# ZED-F9R_v3.net
KiCad netlist of a schematic drawn in EAGLE
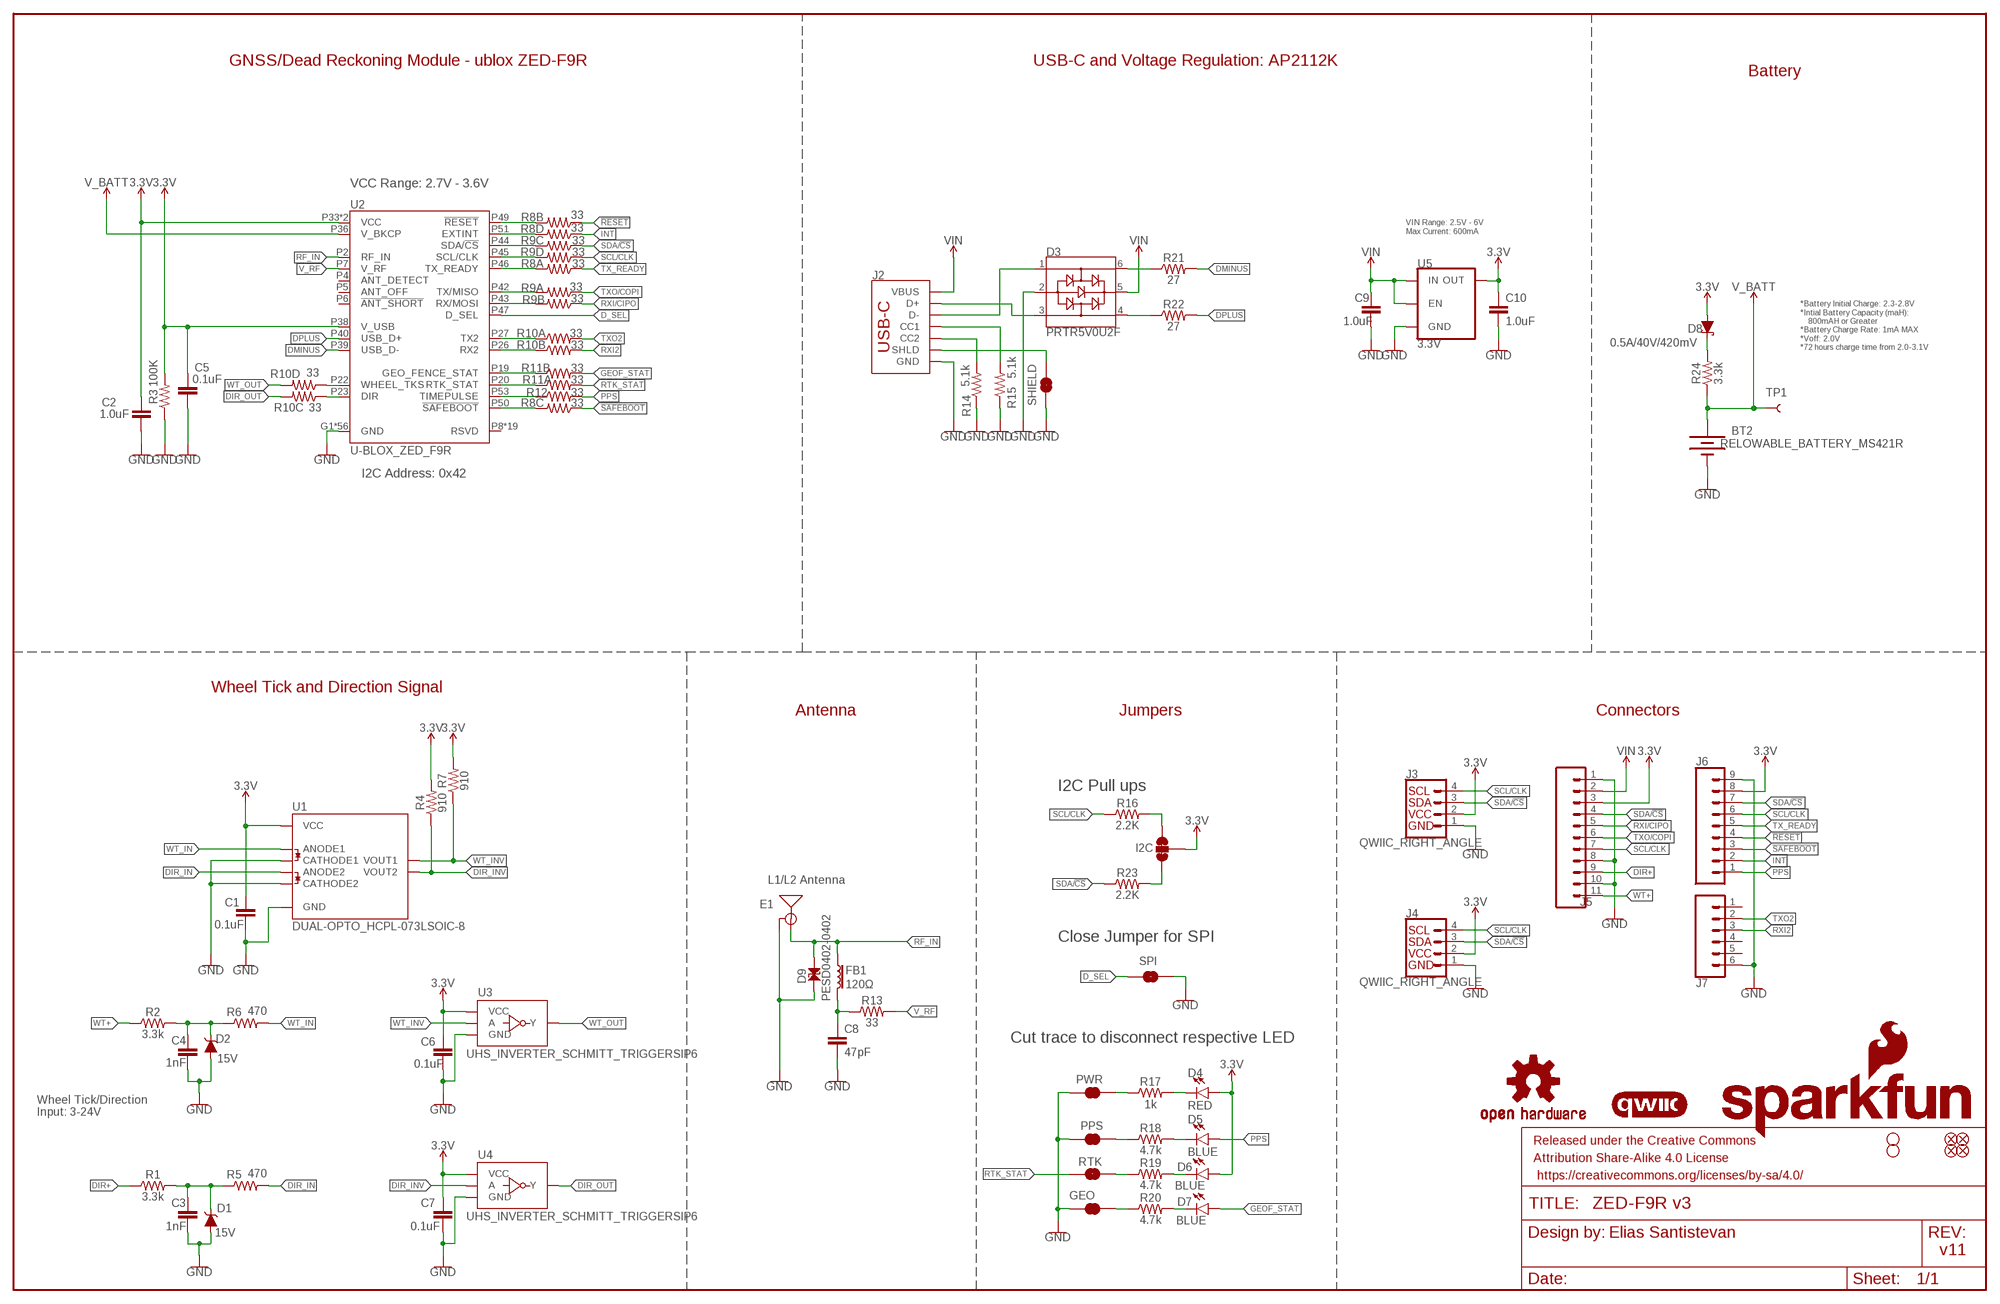
[diagram p0: schematic, sheet 1]

(export (version "E")
  (design (tool "Eeschema 10.0.6"))
  (components
    (comp (ref "$1_25_$_2020-03-30_22-52-05")
      (value "STAND-OFFTIGHT")
      (footprint "eagle-import:STAND-OFF-TIGHT")
      (libsource (lib "eagle-import") (part "STAND-OFFTIGHT"))
    )
    (comp (ref "BT2")
      (value "RELOWABLE_BATTERY_MS421R")
      (footprint "eagle-import:MS421R_IV03E")
      (libsource (lib "eagle-import") (part "RELOWABLE_BATTERY_MS421R"))
    )
    (comp (ref "C1")
      (value "0.1uF")
      (footprint "eagle-import:0402-TIGHT")
      (libsource (lib "eagle-import") (part "0.1UF-0402T-6.3V-10%-X7R"))
    )
    (comp (ref "C2")
      (value "1.0uF")
      (footprint "eagle-import:0402-TIGHT")
      (libsource (lib "eagle-import") (part "1.0UF-0402T-16V-10%"))
    )
    (comp (ref "C3")
      (value "1nF")
      (footprint "eagle-import:0402")
      (libsource (lib "eagle-import") (part "1.0NF/1000PF-0402-25V-10%-X7R"))
    )
    (comp (ref "C4")
      (value "1nF")
      (footprint "eagle-import:0402")
      (libsource (lib "eagle-import") (part "1.0NF/1000PF-0402-25V-10%-X7R"))
    )
    (comp (ref "C5")
      (value "0.1uF")
      (footprint "eagle-import:0402-TIGHT")
      (libsource (lib "eagle-import") (part "0.1UF-0402T-6.3V-10%-X7R"))
    )
    (comp (ref "C6")
      (value "0.1uF")
      (footprint "eagle-import:0402-TIGHT")
      (libsource (lib "eagle-import") (part "0.1UF-0402T-6.3V-10%-X7R"))
    )
    (comp (ref "C7")
      (value "0.1uF")
      (footprint "eagle-import:0402-TIGHT")
      (libsource (lib "eagle-import") (part "0.1UF-0402T-6.3V-10%-X7R"))
    )
    (comp (ref "C8")
      (value "47pF")
      (footprint "eagle-import:0402")
      (libsource (lib "eagle-import") (part "47PF-0402-25V-5%-X7R"))
    )
    (comp (ref "C9")
      (value "1.0uF")
      (footprint "eagle-import:0402-TIGHT")
      (libsource (lib "eagle-import") (part "1.0UF-0402T-16V-10%"))
    )
    (comp (ref "C10")
      (value "1.0uF")
      (footprint "eagle-import:0402-TIGHT")
      (libsource (lib "eagle-import") (part "1.0UF-0402T-16V-10%"))
    )
    (comp (ref "D1")
      (value "15V")
      (footprint "eagle-import:SOT23-3")
      (libsource (lib "eagle-import") (part "DIODE-ZENER-BZX84C15LT3G"))
    )
    (comp (ref "D2")
      (value "15V")
      (footprint "eagle-import:SOT23-3")
      (libsource (lib "eagle-import") (part "DIODE-ZENER-BZX84C15LT3G"))
    )
    (comp (ref "D3")
      (value "PRTR5V0U2F")
      (footprint "eagle-import:SOT886")
      (libsource (lib "eagle-import") (part "PRTR5V0U2F"))
    )
    (comp (ref "D4")
      (value "RED")
      (footprint "eagle-import:LED-0603")
      (libsource (lib "eagle-import") (part "LED-RED0603"))
    )
    (comp (ref "D5")
      (value "BLUE")
      (footprint "eagle-import:LED-0603")
      (libsource (lib "eagle-import") (part "LED-BLUE0603"))
    )
    (comp (ref "D6")
      (value "BLUE")
      (footprint "eagle-import:LED-0603")
      (libsource (lib "eagle-import") (part "LED-BLUE0603"))
    )
    (comp (ref "D7")
      (value "BLUE")
      (footprint "eagle-import:LED-0603")
      (libsource (lib "eagle-import") (part "LED-BLUE0603"))
    )
    (comp (ref "D8")
      (value "0.5A/40V/420mV")
      (footprint "eagle-import:SOD-323")
      (libsource (lib "eagle-import") (part "DIODE-SCHOTTKY-PMEG4005EJ"))
    )
    (comp (ref "D9")
      (value "PESD0402-0402")
      (footprint "eagle-import:0402")
      (fields
        (field (name "DIGIKEY_PART") "PESD0402-140CT-ND")
        (field (name "MOUSE_PART") "650-PESD0402-140")
      )
      (libsource (lib "eagle-import") (part "PESD0402-0402"))
    )
    (comp (ref "E1")
      (value "ANTENNA-SMA-GROUNDEDEDGE_SMA")
      (footprint "eagle-import:SMA-EDGE")
      (libsource (lib "eagle-import") (part "ANTENNA-SMA-GROUNDEDEDGE_SMA"))
    )
    (comp (ref "FB1")
      (value "120Ω")
      (footprint "eagle-import:0402")
      (fields (field (name "MFG_PART") "BLM15HB121SN1D"))
      (libsource (lib "eagle-import") (part "FERRITE_BEAD-120_OHM-0402"))
    )
    (comp (ref "FD1")
      (value "FIDUCIALUFIDUCIAL")
      (footprint "eagle-import:FIDUCIAL-MICRO")
      (libsource (lib "eagle-import") (part "FIDUCIALUFIDUCIAL"))
    )
    (comp (ref "FD2")
      (value "FIDUCIALUFIDUCIAL")
      (footprint "eagle-import:FIDUCIAL-MICRO")
      (libsource (lib "eagle-import") (part "FIDUCIALUFIDUCIAL"))
    )
    (comp (ref "FD3")
      (value "FIDUCIALUFIDUCIAL")
      (footprint "eagle-import:FIDUCIAL-MICRO")
      (libsource (lib "eagle-import") (part "FIDUCIALUFIDUCIAL"))
    )
    (comp (ref "FD4")
      (value "FIDUCIALUFIDUCIAL")
      (footprint "eagle-import:FIDUCIAL-MICRO")
      (libsource (lib "eagle-import") (part "FIDUCIALUFIDUCIAL"))
    )
    (comp (ref "FRAME1")
      (value "FRAME-LEDGER")
      (footprint "eagle-import:CREATIVE_COMMONS")
      (libsource (lib "eagle-import") (part "FRAME-LEDGER"))
    )
    (comp (ref "GEO")
      (value "JUMPER-SMT_2_NC_TRACE_SILK")
      (footprint "eagle-import:SMT-JUMPER_2_NC_TRACE_SILK")
      (libsource (lib "eagle-import") (part "JUMPER-SMT_2_NC_TRACE_SILK"))
    )
    (comp (ref "H2")
      (value "STAND-OFFTIGHT")
      (footprint "eagle-import:STAND-OFF-TIGHT")
      (libsource (lib "eagle-import") (part "STAND-OFFTIGHT"))
    )
    (comp (ref "I2C")
      (value "JUMPER-SMT_3_2-NC_TRACE_SILK")
      (footprint "eagle-import:SMT-JUMPER_3_2-NC_TRACE_SILK")
      (libsource (lib "eagle-import") (part "JUMPER-SMT_3_2-NC_TRACE_SILK"))
    )
    (comp (ref "J2")
      (value "USB_C_2-LAYER_PADS")
      (footprint "eagle-import:USB-C-16P-2LAYER-PADS")
      (libsource (lib "eagle-import") (part "USB_C_2-LAYER_PADS"))
    )
    (comp (ref "J3")
      (value "QWIIC_RIGHT_ANGLE")
      (footprint "eagle-import:JST04_1MM_RA")
      (libsource (lib "eagle-import") (part "QWIIC_CONNECTORJS-1MM"))
    )
    (comp (ref "J4")
      (value "QWIIC_RIGHT_ANGLE")
      (footprint "eagle-import:JST04_1MM_RA")
      (libsource (lib "eagle-import") (part "QWIIC_CONNECTORJS-1MM"))
    )
    (comp (ref "J5")
      (value "CONN_111X11_NO_SILK")
      (footprint "eagle-import:1X11_NO_SILK")
      (libsource (lib "eagle-import") (part "CONN_111X11_NO_SILK"))
    )
    (comp (ref "J6")
      (value "CONN_09NO_SILK")
      (footprint "eagle-import:1X09_NO_SILK")
      (libsource (lib "eagle-import") (part "CONN_09NO_SILK"))
    )
    (comp (ref "J7")
      (value "CONN_06NO_SILK_NO_POP")
      (footprint "eagle-import:1X06_NO_SILK")
      (libsource (lib "eagle-import") (part "CONN_06NO_SILK_NO_POP"))
    )
    (comp (ref "LOGO1")
      (value "OSHW-LOGOS")
      (footprint "eagle-import:OSHW-LOGO-S")
      (libsource (lib "eagle-import") (part "OSHW-LOGOS"))
    )
    (comp (ref "LOGO2")
      (value "QWIIC_LOGO_4MM")
      (footprint "eagle-import:QWIIC_4MM")
      (libsource (lib "eagle-import") (part "QWIIC_LOGO_4MM"))
    )
    (comp (ref "LOGO3")
      (value "SFE_LOGO_NAME_FLAME.2_INCH")
      (footprint "eagle-import:SFE_LOGO_NAME_FLAME_.2")
      (libsource (lib "eagle-import") (part "SFE_LOGO_NAME_FLAME.2_INCH"))
    )
    (comp (ref "PPS")
      (value "JUMPER-SMT_2_NC_TRACE_SILK")
      (footprint "eagle-import:SMT-JUMPER_2_NC_TRACE_SILK")
      (libsource (lib "eagle-import") (part "JUMPER-SMT_2_NC_TRACE_SILK"))
    )
    (comp (ref "PWR")
      (value "JUMPER-SMT_2_NC_TRACE_SILK")
      (footprint "eagle-import:SMT-JUMPER_2_NC_TRACE_SILK")
      (libsource (lib "eagle-import") (part "JUMPER-SMT_2_NC_TRACE_SILK"))
    )
    (comp (ref "R1")
      (value "3.3k")
      (footprint "eagle-import:0603")
      (libsource (lib "eagle-import") (part "3.3KOHM-0603-1/10W-1%"))
    )
    (comp (ref "R2")
      (value "3.3k")
      (footprint "eagle-import:0603")
      (libsource (lib "eagle-import") (part "3.3KOHM-0603-1/10W-1%"))
    )
    (comp (ref "R3")
      (value "100K")
      (footprint "eagle-import:0402")
      (libsource (lib "eagle-import") (part "100KOHM-0402-1/16W-1%"))
    )
    (comp (ref "R4")
      (value "910")
      (footprint "eagle-import:0603")
      (libsource (lib "eagle-import") (part "910OHM-0603-1/10W-5%"))
    )
    (comp (ref "R5")
      (value "470")
      (footprint "eagle-import:0603")
      (libsource (lib "eagle-import") (part "470OHM-0603-1/10W-1%"))
    )
    (comp (ref "R6")
      (value "470")
      (footprint "eagle-import:0603")
      (libsource (lib "eagle-import") (part "470OHM-0603-1/10W-1%"))
    )
    (comp (ref "R7")
      (value "910")
      (footprint "eagle-import:0603")
      (libsource (lib "eagle-import") (part "910OHM-0603-1/10W-5%"))
    )
    (comp (ref "R8")
      (value "33")
      (footprint "eagle-import:1206_RA")
      (libsource (lib "eagle-import") (part "33OHM_RA-1206-1/16W-5%"))
    )
    (comp (ref "R9")
      (value "33")
      (footprint "eagle-import:1206_RA")
      (libsource (lib "eagle-import") (part "33OHM_RA-1206-1/16W-5%"))
    )
    (comp (ref "R10")
      (value "33")
      (footprint "eagle-import:1206_RA")
      (libsource (lib "eagle-import") (part "33OHM_RA-1206-1/16W-5%"))
    )
    (comp (ref "R11")
      (value "33")
      (footprint "eagle-import:1206_RA")
      (libsource (lib "eagle-import") (part "33OHM_RA-1206-1/16W-5%"))
    )
    (comp (ref "R12")
      (value "33")
      (footprint "eagle-import:0603")
      (libsource (lib "eagle-import") (part "33OHM-0603-1/10W-1%"))
    )
    (comp (ref "R13")
      (value "33")
      (footprint "eagle-import:0603")
      (libsource (lib "eagle-import") (part "33OHM-0603-1/10W-1%"))
    )
    (comp (ref "R14")
      (value "5.1k")
      (footprint "eagle-import:0402")
      (libsource (lib "eagle-import") (part "5.1KOHM-0402-1/16W-1%"))
    )
    (comp (ref "R15")
      (value "5.1k")
      (footprint "eagle-import:0402")
      (libsource (lib "eagle-import") (part "5.1KOHM-0402-1/16W-1%"))
    )
    (comp (ref "R16")
      (value "2.2K")
      (footprint "eagle-import:0402")
      (libsource (lib "eagle-import") (part "2.2KOHM-0402-1/16W-1%"))
    )
    (comp (ref "R17")
      (value "1KOHM-0402-1/16W-1%")
      (footprint "eagle-import:0402")
      (libsource (lib "eagle-import") (part "1KOHM-0402-1/16W-1%"))
    )
    (comp (ref "R18")
      (value "4.7k")
      (footprint "eagle-import:0603")
      (libsource (lib "eagle-import") (part "4.7KOHM-0603-1/10W-1%"))
    )
    (comp (ref "R19")
      (value "4.7k")
      (footprint "eagle-import:0603")
      (libsource (lib "eagle-import") (part "4.7KOHM-0603-1/10W-1%"))
    )
    (comp (ref "R20")
      (value "4.7k")
      (footprint "eagle-import:0603")
      (libsource (lib "eagle-import") (part "4.7KOHM-0603-1/10W-1%"))
    )
    (comp (ref "R21")
      (value "27")
      (footprint "eagle-import:0603")
      (libsource (lib "eagle-import") (part "27OHM-0603-1/10W-1%"))
    )
    (comp (ref "R22")
      (value "27")
      (footprint "eagle-import:0603")
      (libsource (lib "eagle-import") (part "27OHM-0603-1/10W-1%"))
    )
    (comp (ref "R23")
      (value "2.2K")
      (footprint "eagle-import:0402")
      (libsource (lib "eagle-import") (part "2.2KOHM-0402-1/16W-1%"))
    )
    (comp (ref "R24")
      (value "3.3k")
      (footprint "eagle-import:0603")
      (libsource (lib "eagle-import") (part "3.3KOHM-0603-1/10W-1%"))
    )
    (comp (ref "RTK")
      (value "JUMPER-SMT_2_NC_TRACE_SILK")
      (footprint "eagle-import:SMT-JUMPER_2_NC_TRACE_SILK")
      (libsource (lib "eagle-import") (part "JUMPER-SMT_2_NC_TRACE_SILK"))
    )
    (comp (ref "SHIELD")
      (value "JUMPER-SMT_2_NC_TRACE_SILK")
      (footprint "eagle-import:SMT-JUMPER_2_NC_TRACE_SILK")
      (libsource (lib "eagle-import") (part "JUMPER-SMT_2_NC_TRACE_SILK"))
    )
    (comp (ref "SPI")
      (value "JUMPER-SMT_2_NO_SILK")
      (footprint "eagle-import:SMT-JUMPER_2_NO_SILK")
      (libsource (lib "eagle-import") (part "JUMPER-SMT_2_NO_SILK"))
    )
    (comp (ref "TP1")
      (value "TEST-POINT3X5")
      (footprint "eagle-import:PAD.03X.05")
      (libsource (lib "eagle-import") (part "TEST-POINT3X5"))
    )
    (comp (ref "U1")
      (value "DUAL-OPTO_HCPL-073LSOIC-8")
      (footprint "eagle-import:SO08")
      (libsource (lib "eagle-import") (part "DUAL-OPTO_HCPL-073LSOIC-8"))
    )
    (comp (ref "U2")
      (value "U-BLOX_ZED_F9R")
      (footprint "eagle-import:UBLOX_ZED_F9R")
      (libsource (lib "eagle-import") (part "U-BLOX_ZED_F9R"))
    )
    (comp (ref "U3")
      (value "UHS_INVERTER_SCHMITT_TRIGGERSIP6")
      (footprint "eagle-import:SIP6_MICROPAK2")
      (libsource (lib "eagle-import") (part "UHS_INVERTER_SCHMITT_TRIGGER_MPAK2"))
    )
    (comp (ref "U4")
      (value "UHS_INVERTER_SCHMITT_TRIGGERSIP6")
      (footprint "eagle-import:SIP6_MICROPAK2")
      (libsource (lib "eagle-import") (part "UHS_INVERTER_SCHMITT_TRIGGER_MPAK2"))
    )
    (comp (ref "U5")
      (value "3.3V")
      (footprint "eagle-import:SOT23-5")
      (libsource (lib "eagle-import") (part "V_REG_AP2112K-3.3V"))
    )
  )
  (nets
    (net (code "1") (name "/SDA{slash}~{CS}") (class "Default")
      (node (ref "J3") (pin "3") (pinfunction "3_3") (pintype "passive"))
      (node (ref "J4") (pin "3") (pinfunction "3_3") (pintype "passive"))
      (node (ref "J5") (pin "4") (pinfunction "4_4") (pintype "passive"))
      (node (ref "J6") (pin "7") (pinfunction "7_7") (pintype "passive"))
      (node (ref "R23") (pin "1") (pinfunction "1_1") (pintype "passive"))
      (node (ref "R9") (pin "P3") (pinfunction "1_P3") (pintype "passive"))
    )
    (net (code "2") (name "/~{RESET}") (class "Default")
      (node (ref "J6") (pin "4") (pinfunction "4_4") (pintype "passive"))
      (node (ref "R8") (pin "P2") (pinfunction "1_P2") (pintype "passive"))
    )
    (net (code "3") (name "/~{SAFEBOOT}") (class "Default")
      (node (ref "J6") (pin "3") (pinfunction "3_3") (pintype "passive"))
      (node (ref "R8") (pin "P3") (pinfunction "1_P3") (pintype "passive"))
    )
    (net (code "4") (name "3.3V") (class "Default")
      (node (ref "C1") (pin "1") (pinfunction "1_1") (pintype "passive"))
      (node (ref "C10") (pin "1") (pinfunction "1_1") (pintype "passive"))
      (node (ref "C2") (pin "1") (pinfunction "1_1") (pintype "passive"))
      (node (ref "C5") (pin "1") (pinfunction "1_1") (pintype "passive"))
      (node (ref "C6") (pin "1") (pinfunction "1_1") (pintype "passive"))
      (node (ref "C7") (pin "1") (pinfunction "1_1") (pintype "passive"))
      (node (ref "D4") (pin "A") (pinfunction "A_A") (pintype "passive"))
      (node (ref "D6") (pin "A") (pinfunction "A_A") (pintype "passive"))
      (node (ref "D8") (pin "A") (pinfunction "A_A") (pintype "passive"))
      (node (ref "I2C") (pin "2") (pinfunction "2_2") (pintype "passive"))
      (node (ref "J3") (pin "2") (pinfunction "2_2") (pintype "power_in"))
      (node (ref "J4") (pin "2") (pinfunction "2_2") (pintype "power_in"))
      (node (ref "J5") (pin "3") (pinfunction "3_3") (pintype "passive"))
      (node (ref "J6") (pin "8") (pinfunction "8_8") (pintype "passive"))
      (node (ref "R3") (pin "2") (pinfunction "2_2") (pintype "passive"))
      (node (ref "R4") (pin "2") (pinfunction "2_2") (pintype "passive"))
      (node (ref "R7") (pin "2") (pinfunction "2_2") (pintype "passive"))
      (node (ref "U1") (pin "8") (pinfunction "VCC_8") (pintype "power_in"))
      (node (ref "U2") (pin "P33") (pinfunction "VCC_P33") (pintype "power_in"))
      (node (ref "U2") (pin "P34") (pinfunction "VCC_P34") (pintype "power_in"))
      (node (ref "U2") (pin "P38") (pinfunction "V_USB_P38") (pintype "power_in"))
      (node (ref "U3") (pin "P6") (pinfunction "VCC_P6") (pintype "power_in"))
      (node (ref "U4") (pin "P6") (pinfunction "VCC_P6") (pintype "power_in"))
      (node (ref "U5") (pin "5") (pinfunction "OUT_5") (pintype "passive"))
    )
    (net (code "5") (name "DIR+") (class "Default")
      (node (ref "J5") (pin "9") (pinfunction "9_9") (pintype "passive"))
      (node (ref "R1") (pin "1") (pinfunction "1_1") (pintype "passive"))
    )
    (net (code "6") (name "DIR_IN") (class "Default")
      (node (ref "R5") (pin "2") (pinfunction "2_2") (pintype "passive"))
      (node (ref "U1") (pin "4") (pinfunction "ANODE2_4") (pintype "input"))
    )
    (net (code "7") (name "DIR_INV") (class "Default")
      (node (ref "R4") (pin "1") (pinfunction "1_1") (pintype "passive"))
      (node (ref "U1") (pin "6") (pinfunction "VOUT2_6") (pintype "output"))
      (node (ref "U4") (pin "P2") (pinfunction "A_P2") (pintype "input"))
    )
    (net (code "8") (name "DIR_OUT") (class "Default")
      (node (ref "R10") (pin "P6") (pinfunction "2_P6") (pintype "passive"))
      (node (ref "U4") (pin "P4") (pinfunction "Y_P4") (pintype "output"))
    )
    (net (code "9") (name "DMINUS") (class "Default")
      (node (ref "R21") (pin "2") (pinfunction "2_2") (pintype "passive"))
      (node (ref "U2") (pin "P39") (pinfunction "USB_D-_P39") (pintype "bidirectional"))
    )
    (net (code "10") (name "DPLUS") (class "Default")
      (node (ref "R22") (pin "2") (pinfunction "2_2") (pintype "passive"))
      (node (ref "U2") (pin "P40") (pinfunction "USB_D+_P40") (pintype "bidirectional"))
    )
    (net (code "11") (name "D_SEL") (class "Default")
      (node (ref "SPI") (pin "1") (pinfunction "1_1") (pintype "passive"))
      (node (ref "U2") (pin "P47") (pinfunction "D_SEL_P47") (pintype "bidirectional"))
    )
    (net (code "12") (name "GEOF_STAT") (class "Default")
      (node (ref "D7") (pin "A") (pinfunction "A_A") (pintype "passive"))
      (node (ref "R11") (pin "P7") (pinfunction "2_P7") (pintype "passive"))
    )
    (net (code "13") (name "GND") (class "Default")
      (node (ref "BT2") (pin "-") (pinfunction "-_-") (pintype "power_in"))
      (node (ref "C1") (pin "2") (pinfunction "2_2") (pintype "passive"))
      (node (ref "C10") (pin "2") (pinfunction "2_2") (pintype "passive"))
      (node (ref "C2") (pin "2") (pinfunction "2_2") (pintype "passive"))
      (node (ref "C3") (pin "2") (pinfunction "2_2") (pintype "passive"))
      (node (ref "C4") (pin "2") (pinfunction "2_2") (pintype "passive"))
      (node (ref "C5") (pin "2") (pinfunction "2_2") (pintype "passive"))
      (node (ref "C6") (pin "2") (pinfunction "2_2") (pintype "passive"))
      (node (ref "C7") (pin "2") (pinfunction "2_2") (pintype "passive"))
      (node (ref "C8") (pin "2") (pinfunction "2_2") (pintype "passive"))
      (node (ref "C9") (pin "2") (pinfunction "2_2") (pintype "passive"))
      (node (ref "D1") (pin "1") (pinfunction "A_1") (pintype "passive"))
      (node (ref "D2") (pin "1") (pinfunction "A_1") (pintype "passive"))
      (node (ref "D3") (pin "2") (pinfunction "2_2") (pintype "power_in"))
      (node (ref "D9") (pin "1") (pinfunction "1_1") (pintype "bidirectional"))
      (node (ref "E1") (pin "GND@0") (pinfunction "GND_GND@0") (pintype "bidirectional"))
      (node (ref "E1") (pin "GND@1") (pinfunction "GND_GND@1") (pintype "bidirectional"))
      (node (ref "E1") (pin "GND@2") (pinfunction "GND_GND@2") (pintype "bidirectional"))
      (node (ref "E1") (pin "GND@3") (pinfunction "GND_GND@3") (pintype "bidirectional"))
      (node (ref "GEO") (pin "1") (pinfunction "1_1") (pintype "passive"))
      (node (ref "J2") (pin "GND") (pinfunction "GND_GND") (pintype "bidirectional"))
      (node (ref "J2") (pin "GND2") (pinfunction "GND_GND2") (pintype "bidirectional"))
      (node (ref "J3") (pin "1") (pinfunction "1_1") (pintype "power_in"))
      (node (ref "J4") (pin "1") (pinfunction "1_1") (pintype "power_in"))
      (node (ref "J5") (pin "1") (pinfunction "1_1") (pintype "passive"))
      (node (ref "J5") (pin "10") (pinfunction "10_10") (pintype "passive"))
      (node (ref "J5") (pin "8") (pinfunction "8_8") (pintype "passive"))
      (node (ref "J6") (pin "9") (pinfunction "9_9") (pintype "passive"))
      (node (ref "J7") (pin "6") (pinfunction "6_6") (pintype "passive"))
      (node (ref "PPS") (pin "1") (pinfunction "1_1") (pintype "passive"))
      (node (ref "PWR") (pin "1") (pinfunction "1_1") (pintype "passive"))
      (node (ref "R14") (pin "1") (pinfunction "1_1") (pintype "passive"))
      (node (ref "R15") (pin "1") (pinfunction "1_1") (pintype "passive"))
      (node (ref "R3") (pin "1") (pinfunction "1_1") (pintype "passive"))
      (node (ref "SHIELD") (pin "1") (pinfunction "1_1") (pintype "passive"))
      (node (ref "SPI") (pin "2") (pinfunction "2_2") (pintype "passive"))
      (node (ref "U1") (pin "2") (pinfunction "CATHODE1_2") (pintype "input"))
      (node (ref "U1") (pin "3") (pinfunction "CATHODE2_3") (pintype "input"))
      (node (ref "U1") (pin "5") (pinfunction "GND_5") (pintype "power_in"))
      (node (ref "U2") (pin "G1") (pinfunction "GND_G1") (pintype "power_in"))
      (node (ref "U2") (pin "G10") (pinfunction "GND_G10") (pintype "power_in"))
      (node (ref "U2") (pin "G11") (pinfunction "GND_G11") (pintype "power_in"))
      (node (ref "U2") (pin "G12") (pinfunction "GND_G12") (pintype "power_in"))
      (node (ref "U2") (pin "G13") (pinfunction "GND_G13") (pintype "power_in"))
      (node (ref "U2") (pin "G14") (pinfunction "GND_G14") (pintype "power_in"))
      (node (ref "U2") (pin "G15") (pinfunction "GND_G15") (pintype "power_in"))
      (node (ref "U2") (pin "G16") (pinfunction "GND_G16") (pintype "power_in"))
      (node (ref "U2") (pin "G17") (pinfunction "GND_G17") (pintype "power_in"))
      (node (ref "U2") (pin "G18") (pinfunction "GND_G18") (pintype "power_in"))
      (node (ref "U2") (pin "G19") (pinfunction "GND_G19") (pintype "power_in"))
      (node (ref "U2") (pin "G2") (pinfunction "GND_G2") (pintype "power_in"))
      (node (ref "U2") (pin "G20") (pinfunction "GND_G20") (pintype "power_in"))
      (node (ref "U2") (pin "G21") (pinfunction "GND_G21") (pintype "power_in"))
      (node (ref "U2") (pin "G22") (pinfunction "GND_G22") (pintype "power_in"))
      (node (ref "U2") (pin "G23") (pinfunction "GND_G23") (pintype "power_in"))
      (node (ref "U2") (pin "G24") (pinfunction "GND_G24") (pintype "power_in"))
      (node (ref "U2") (pin "G25") (pinfunction "GND_G25") (pintype "power_in"))
      (node (ref "U2") (pin "G26") (pinfunction "GND_G26") (pintype "power_in"))
      (node (ref "U2") (pin "G27") (pinfunction "GND_G27") (pintype "power_in"))
      (node (ref "U2") (pin "G28") (pinfunction "GND_G28") (pintype "power_in"))
      (node (ref "U2") (pin "G29") (pinfunction "GND_G29") (pintype "power_in"))
      (node (ref "U2") (pin "G3") (pinfunction "GND_G3") (pintype "power_in"))
      (node (ref "U2") (pin "G30") (pinfunction "GND_G30") (pintype "power_in"))
      (node (ref "U2") (pin "G31") (pinfunction "GND_G31") (pintype "power_in"))
      (node (ref "U2") (pin "G32") (pinfunction "GND_G32") (pintype "power_in"))
      (node (ref "U2") (pin "G33") (pinfunction "GND_G33") (pintype "power_in"))
      (node (ref "U2") (pin "G34") (pinfunction "GND_G34") (pintype "power_in"))
      (node (ref "U2") (pin "G35") (pinfunction "GND_G35") (pintype "power_in"))
      (node (ref "U2") (pin "G36") (pinfunction "GND_G36") (pintype "power_in"))
      (node (ref "U2") (pin "G37") (pinfunction "GND_G37") (pintype "power_in"))
      (node (ref "U2") (pin "G38") (pinfunction "GND_G38") (pintype "power_in"))
      (node (ref "U2") (pin "G39") (pinfunction "GND_G39") (pintype "power_in"))
      (node (ref "U2") (pin "G4") (pinfunction "GND_G4") (pintype "power_in"))
      (node (ref "U2") (pin "G40") (pinfunction "GND_G40") (pintype "power_in"))
      (node (ref "U2") (pin "G41") (pinfunction "GND_G41") (pintype "power_in"))
      (node (ref "U2") (pin "G42") (pinfunction "GND_G42") (pintype "power_in"))
      (node (ref "U2") (pin "G43") (pinfunction "GND_G43") (pintype "power_in"))
      (node (ref "U2") (pin "G44") (pinfunction "GND_G44") (pintype "power_in"))
      (node (ref "U2") (pin "G45") (pinfunction "GND_G45") (pintype "power_in"))
      (node (ref "U2") (pin "G46") (pinfunction "GND_G46") (pintype "power_in"))
      (node (ref "U2") (pin "G47") (pinfunction "GND_G47") (pintype "power_in"))
      (node (ref "U2") (pin "G48") (pinfunction "GND_G48") (pintype "power_in"))
      (node (ref "U2") (pin "G5") (pinfunction "GND_G5") (pintype "power_in"))
      (node (ref "U2") (pin "G6") (pinfunction "GND_G6") (pintype "power_in"))
      (node (ref "U2") (pin "G7") (pinfunction "GND_G7") (pintype "power_in"))
      (node (ref "U2") (pin "G8") (pinfunction "GND_G8") (pintype "power_in"))
      (node (ref "U2") (pin "G9") (pinfunction "GND_G9") (pintype "power_in"))
      (node (ref "U2") (pin "P1") (pinfunction "GND_P1") (pintype "power_in"))
      (node (ref "U2") (pin "P12") (pinfunction "GND_P12") (pintype "power_in"))
      (node (ref "U2") (pin "P14") (pinfunction "GND_P14") (pintype "power_in"))
      (node (ref "U2") (pin "P3") (pinfunction "GND_P3") (pintype "power_in"))
      (node (ref "U2") (pin "P32") (pinfunction "GND_P32") (pintype "power_in"))
      (node (ref "U2") (pin "P37") (pinfunction "GND_P37") (pintype "power_in"))
      (node (ref "U2") (pin "P41") (pinfunction "GND_P41") (pintype "power_in"))
      (node (ref "U2") (pin "P48") (pinfunction "GND_P48") (pintype "power_in"))
      (node (ref "U3") (pin "P3") (pinfunction "GND_P3") (pintype "power_in"))
      (node (ref "U4") (pin "P3") (pinfunction "GND_P3") (pintype "power_in"))
      (node (ref "U5") (pin "2") (pinfunction "GND_2") (pintype "input"))
    )
    (net (code "14") (name "INT") (class "Default")
      (node (ref "J6") (pin "2") (pinfunction "2_2") (pintype "passive"))
      (node (ref "R8") (pin "P4") (pinfunction "1_P4") (pintype "passive"))
    )
    (net (code "15") (name "Net-(C8-Pad1)") (class "Default")
      (node (ref "C8") (pin "1") (pinfunction "1_1") (pintype "passive"))
      (node (ref "FB1") (pin "2") (pinfunction "2_2") (pintype "passive"))
      (node (ref "R13") (pin "1") (pinfunction "1_1") (pintype "passive"))
    )
    (net (code "16") (name "Net-(D1-C)") (class "Default")
      (node (ref "C3") (pin "1") (pinfunction "1_1") (pintype "passive"))
      (node (ref "D1") (pin "3") (pinfunction "C_3") (pintype "passive"))
      (node (ref "R1") (pin "2") (pinfunction "2_2") (pintype "passive"))
      (node (ref "R5") (pin "1") (pinfunction "1_1") (pintype "passive"))
    )
    (net (code "17") (name "Net-(D2-C)") (class "Default")
      (node (ref "C4") (pin "1") (pinfunction "1_1") (pintype "passive"))
      (node (ref "D2") (pin "3") (pinfunction "C_3") (pintype "passive"))
      (node (ref "R2") (pin "2") (pinfunction "2_2") (pintype "passive"))
      (node (ref "R6") (pin "1") (pinfunction "1_1") (pintype "passive"))
    )
    (net (code "18") (name "Net-(D3-Pad1)") (class "Default")
      (node (ref "D3") (pin "1") (pinfunction "1_1") (pintype "bidirectional"))
      (node (ref "J2") (pin "A7") (pinfunction "D-_A7") (pintype "bidirectional"))
      (node (ref "J2") (pin "B7") (pinfunction "D-_B7") (pintype "bidirectional"))
    )
    (net (code "19") (name "Net-(D3-Pad3)") (class "Default")
      (node (ref "D3") (pin "3") (pinfunction "3_3") (pintype "bidirectional"))
      (node (ref "J2") (pin "A6") (pinfunction "D+_A6") (pintype "bidirectional"))
      (node (ref "J2") (pin "B6") (pinfunction "D+_B6") (pintype "bidirectional"))
    )
    (net (code "20") (name "Net-(D3-Pad4)") (class "Default")
      (node (ref "D3") (pin "4") (pinfunction "4_4") (pintype "bidirectional"))
      (node (ref "R22") (pin "1") (pinfunction "1_1") (pintype "passive"))
    )
    (net (code "21") (name "Net-(D3-Pad6)") (class "Default")
      (node (ref "D3") (pin "6") (pinfunction "6_6") (pintype "bidirectional"))
      (node (ref "R21") (pin "1") (pinfunction "1_1") (pintype "passive"))
    )
    (net (code "22") (name "Net-(D4-PadC)") (class "Default")
      (node (ref "D4") (pin "C") (pinfunction "C_C") (pintype "passive"))
      (node (ref "R17") (pin "2") (pinfunction "2_2") (pintype "passive"))
    )
    (net (code "23") (name "Net-(D5-PadC)") (class "Default")
      (node (ref "D5") (pin "C") (pinfunction "C_C") (pintype "passive"))
      (node (ref "R18") (pin "2") (pinfunction "2_2") (pintype "passive"))
    )
    (net (code "24") (name "Net-(D6-PadC)") (class "Default")
      (node (ref "D6") (pin "C") (pinfunction "C_C") (pintype "passive"))
      (node (ref "R19") (pin "2") (pinfunction "2_2") (pintype "passive"))
    )
    (net (code "25") (name "Net-(D7-PadC)") (class "Default")
      (node (ref "D7") (pin "C") (pinfunction "C_C") (pintype "passive"))
      (node (ref "R20") (pin "2") (pinfunction "2_2") (pintype "passive"))
    )
    (net (code "26") (name "Net-(D8-PadC)") (class "Default")
      (node (ref "D8") (pin "C") (pinfunction "C_C") (pintype "passive"))
      (node (ref "R24") (pin "2") (pinfunction "2_2") (pintype "passive"))
    )
    (net (code "27") (name "Net-(GEO-Pad2)") (class "Default")
      (node (ref "GEO") (pin "2") (pinfunction "2_2") (pintype "passive"))
      (node (ref "R20") (pin "1") (pinfunction "1_1") (pintype "passive"))
    )
    (net (code "28") (name "Net-(I2C-Pad1)") (class "Default")
      (node (ref "I2C") (pin "1") (pinfunction "1_1") (pintype "passive"))
      (node (ref "R23") (pin "2") (pinfunction "2_2") (pintype "passive"))
    )
    (net (code "29") (name "Net-(I2C-Pad3)") (class "Default")
      (node (ref "I2C") (pin "3") (pinfunction "3_3") (pintype "passive"))
      (node (ref "R16") (pin "2") (pinfunction "2_2") (pintype "passive"))
    )
    (net (code "30") (name "Net-(J2-CC1)") (class "Default")
      (node (ref "J2") (pin "A5") (pinfunction "CC1_A5") (pintype "bidirectional"))
      (node (ref "R15") (pin "2") (pinfunction "2_2") (pintype "passive"))
    )
    (net (code "31") (name "Net-(J2-CC2)") (class "Default")
      (node (ref "J2") (pin "B5") (pinfunction "CC2_B5") (pintype "bidirectional"))
      (node (ref "R14") (pin "2") (pinfunction "2_2") (pintype "passive"))
    )
    (net (code "32") (name "Net-(J2-SHLD-PadSHLD1)") (class "Default")
      (node (ref "J2") (pin "SHLD1") (pinfunction "SHLD_SHLD1") (pintype "bidirectional"))
      (node (ref "J2") (pin "SHLD2") (pinfunction "SHLD_SHLD2") (pintype "bidirectional"))
      (node (ref "J2") (pin "SHLD3") (pinfunction "SHLD_SHLD3") (pintype "bidirectional"))
      (node (ref "J2") (pin "SHLD4") (pinfunction "SHLD_SHLD4") (pintype "bidirectional"))
      (node (ref "SHIELD") (pin "2") (pinfunction "2_2") (pintype "passive"))
    )
    (net (code "33") (name "Net-(PPS-Pad2)") (class "Default")
      (node (ref "PPS") (pin "2") (pinfunction "2_2") (pintype "passive"))
      (node (ref "R18") (pin "1") (pinfunction "1_1") (pintype "passive"))
    )
    (net (code "34") (name "Net-(PWR-Pad2)") (class "Default")
      (node (ref "PWR") (pin "2") (pinfunction "2_2") (pintype "passive"))
      (node (ref "R17") (pin "1") (pinfunction "1_1") (pintype "passive"))
    )
    (net (code "35") (name "Net-(R8A-2)") (class "Default")
      (node (ref "R8") (pin "P8") (pinfunction "2_P8") (pintype "passive"))
      (node (ref "U2") (pin "P46") (pinfunction "TX_READY_P46") (pintype "bidirectional"))
    )
    (net (code "36") (name "Net-(R8B-2)") (class "Default")
      (node (ref "R8") (pin "P7") (pinfunction "2_P7") (pintype "passive"))
      (node (ref "U2") (pin "P49") (pinfunction "~{RESET}_P49") (pintype "bidirectional"))
    )
    (net (code "37") (name "Net-(R8C-2)") (class "Default")
      (node (ref "R8") (pin "P6") (pinfunction "2_P6") (pintype "passive"))
      (node (ref "U2") (pin "P50") (pinfunction "~{SAFEBOOT}_P50") (pintype "input"))
    )
    (net (code "38") (name "Net-(R8D-2)") (class "Default")
      (node (ref "R8") (pin "P5") (pinfunction "2_P5") (pintype "passive"))
      (node (ref "U2") (pin "P51") (pinfunction "EXTINT_P51") (pintype "bidirectional"))
    )
    (net (code "39") (name "Net-(R9A-2)") (class "Default")
      (node (ref "R9") (pin "P8") (pinfunction "2_P8") (pintype "passive"))
      (node (ref "U2") (pin "P42") (pinfunction "TX/MISO_P42") (pintype "bidirectional"))
    )
    (net (code "40") (name "Net-(R9B-2)") (class "Default")
      (node (ref "R9") (pin "P7") (pinfunction "2_P7") (pintype "passive"))
      (node (ref "U2") (pin "P43") (pinfunction "RX/MOSI_P43") (pintype "bidirectional"))
    )
    (net (code "41") (name "Net-(R9C-2)") (class "Default")
      (node (ref "R9") (pin "P6") (pinfunction "2_P6") (pintype "passive"))
      (node (ref "U2") (pin "P44") (pinfunction "SDA/~{CS}_P44") (pintype "bidirectional"))
    )
    (net (code "42") (name "Net-(R9D-2)") (class "Default")
      (node (ref "R9") (pin "P5") (pinfunction "2_P5") (pintype "passive"))
      (node (ref "U2") (pin "P45") (pinfunction "SCL/CLK_P45") (pintype "bidirectional"))
    )
    (net (code "43") (name "Net-(R10A-1)") (class "Default")
      (node (ref "R10") (pin "P1") (pinfunction "1_P1") (pintype "passive"))
      (node (ref "U2") (pin "P27") (pinfunction "TX2_P27") (pintype "output"))
    )
    (net (code "44") (name "Net-(R10B-1)") (class "Default")
      (node (ref "R10") (pin "P2") (pinfunction "1_P2") (pintype "passive"))
      (node (ref "U2") (pin "P26") (pinfunction "RX2_P26") (pintype "input"))
    )
    (net (code "45") (name "Net-(R10C-1)") (class "Default")
      (node (ref "R10") (pin "P3") (pinfunction "1_P3") (pintype "passive"))
      (node (ref "U2") (pin "P23") (pinfunction "DIR_P23") (pintype "input"))
    )
    (net (code "46") (name "Net-(R10D-1)") (class "Default")
      (node (ref "R10") (pin "P4") (pinfunction "1_P4") (pintype "passive"))
      (node (ref "U2") (pin "P22") (pinfunction "WHEEL_TKS_P22") (pintype "input"))
    )
    (net (code "47") (name "Net-(R11A-1)") (class "Default")
      (node (ref "R11") (pin "P1") (pinfunction "1_P1") (pintype "passive"))
      (node (ref "U2") (pin "P20") (pinfunction "RTK_STAT_P20") (pintype "output"))
    )
    (net (code "48") (name "Net-(R11B-1)") (class "Default")
      (node (ref "R11") (pin "P2") (pinfunction "1_P2") (pintype "passive"))
      (node (ref "U2") (pin "P19") (pinfunction "GEO_FENCE_STAT_P19") (pintype "output"))
    )
    (net (code "49") (name "Net-(R19-Pad1)") (class "Default")
      (node (ref "R19") (pin "1") (pinfunction "1_1") (pintype "passive"))
      (node (ref "RTK") (pin "2") (pinfunction "2_2") (pintype "passive"))
    )
    (net (code "50") (name "Net-(U2-TIMEPULSE)") (class "Default")
      (node (ref "R12") (pin "1") (pinfunction "1_1") (pintype "passive"))
      (node (ref "U2") (pin "P53") (pinfunction "TIMEPULSE_P53") (pintype "output"))
    )
    (net (code "51") (name "PPS") (class "Default")
      (node (ref "D5") (pin "A") (pinfunction "A_A") (pintype "passive"))
      (node (ref "J6") (pin "1") (pinfunction "1_1") (pintype "passive"))
      (node (ref "R12") (pin "2") (pinfunction "2_2") (pintype "passive"))
    )
    (net (code "52") (name "RF_IN") (class "Default")
      (node (ref "D9") (pin "2") (pinfunction "2_2") (pintype "bidirectional"))
      (node (ref "E1") (pin "SIG") (pinfunction "SIGNAL_SIG") (pintype "bidirectional"))
      (node (ref "FB1") (pin "1") (pinfunction "1_1") (pintype "passive"))
      (node (ref "U2") (pin "P2") (pinfunction "RF_IN_P2") (pintype "input"))
    )
    (net (code "53") (name "RTK_STAT") (class "Default")
      (node (ref "R11") (pin "P8") (pinfunction "2_P8") (pintype "passive"))
      (node (ref "RTK") (pin "1") (pinfunction "1_1") (pintype "passive"))
    )
    (net (code "54") (name "RXI2") (class "Default")
      (node (ref "J7") (pin "3") (pinfunction "3_3") (pintype "passive"))
      (node (ref "R10") (pin "P7") (pinfunction "2_P7") (pintype "passive"))
    )
    (net (code "55") (name "RXI{slash}CIPO") (class "Default")
      (node (ref "J5") (pin "5") (pinfunction "5_5") (pintype "passive"))
      (node (ref "R9") (pin "P2") (pinfunction "1_P2") (pintype "passive"))
    )
    (net (code "56") (name "SCL{slash}CLK") (class "Default")
      (node (ref "J3") (pin "4") (pinfunction "4_4") (pintype "passive"))
      (node (ref "J4") (pin "4") (pinfunction "4_4") (pintype "passive"))
      (node (ref "J5") (pin "7") (pinfunction "7_7") (pintype "passive"))
      (node (ref "J6") (pin "6") (pinfunction "6_6") (pintype "passive"))
      (node (ref "R16") (pin "1") (pinfunction "1_1") (pintype "passive"))
      (node (ref "R9") (pin "P4") (pinfunction "1_P4") (pintype "passive"))
    )
    (net (code "57") (name "TXO2") (class "Default")
      (node (ref "J7") (pin "2") (pinfunction "2_2") (pintype "passive"))
      (node (ref "R10") (pin "P8") (pinfunction "2_P8") (pintype "passive"))
    )
    (net (code "58") (name "TXO{slash}COPI") (class "Default")
      (node (ref "J5") (pin "6") (pinfunction "6_6") (pintype "passive"))
      (node (ref "R9") (pin "P1") (pinfunction "1_P1") (pintype "passive"))
    )
    (net (code "59") (name "TX_READY") (class "Default")
      (node (ref "J6") (pin "5") (pinfunction "5_5") (pintype "passive"))
      (node (ref "R8") (pin "P1") (pinfunction "1_P1") (pintype "passive"))
    )
    (net (code "60") (name "VIN") (class "Default")
      (node (ref "C9") (pin "1") (pinfunction "1_1") (pintype "passive"))
      (node (ref "D3") (pin "5") (pinfunction "5_5") (pintype "power_in"))
      (node (ref "J2") (pin "VBUS1") (pinfunction "VBUS_VBUS1") (pintype "bidirectional"))
      (node (ref "J2") (pin "VBUS2") (pinfunction "VBUS_VBUS2") (pintype "bidirectional"))
      (node (ref "J5") (pin "2") (pinfunction "2_2") (pintype "passive"))
      (node (ref "U5") (pin "1") (pinfunction "IN_1") (pintype "input"))
      (node (ref "U5") (pin "3") (pinfunction "EN_3") (pintype "input"))
    )
    (net (code "61") (name "V_BATT") (class "Default")
      (node (ref "BT2") (pin "+") (pinfunction "+_+") (pintype "power_in"))
      (node (ref "R24") (pin "1") (pinfunction "1_1") (pintype "passive"))
      (node (ref "TP1") (pin "1") (pinfunction "1_1") (pintype "bidirectional"))
      (node (ref "U2") (pin "P36") (pinfunction "V_BKCP_P36") (pintype "power_in"))
    )
    (net (code "62") (name "V_RF") (class "Default")
      (node (ref "R13") (pin "2") (pinfunction "2_2") (pintype "passive"))
      (node (ref "U2") (pin "P7") (pinfunction "V_RF_P7") (pintype "output"))
    )
    (net (code "63") (name "WT+") (class "Default")
      (node (ref "J5") (pin "11") (pinfunction "11_11") (pintype "passive"))
      (node (ref "R2") (pin "1") (pinfunction "1_1") (pintype "passive"))
    )
    (net (code "64") (name "WT_IN") (class "Default")
      (node (ref "R6") (pin "2") (pinfunction "2_2") (pintype "passive"))
      (node (ref "U1") (pin "1") (pinfunction "ANODE1_1") (pintype "input"))
    )
    (net (code "65") (name "WT_INV") (class "Default")
      (node (ref "R7") (pin "1") (pinfunction "1_1") (pintype "passive"))
      (node (ref "U1") (pin "7") (pinfunction "VOUT1_7") (pintype "output"))
      (node (ref "U3") (pin "P2") (pinfunction "A_P2") (pintype "input"))
    )
    (net (code "66") (name "WT_OUT") (class "Default")
      (node (ref "R10") (pin "P5") (pinfunction "2_P5") (pintype "passive"))
      (node (ref "U3") (pin "P4") (pinfunction "Y_P4") (pintype "output"))
    )
    (net (code "67") (name "unconnected-(J7-Pad1)") (class "Default")
      (node (ref "J7") (pin "1") (pinfunction "1_1") (pintype "passive"))
    )
    (net (code "68") (name "unconnected-(J7-Pad4)") (class "Default")
      (node (ref "J7") (pin "4") (pinfunction "4_4") (pintype "passive"))
    )
    (net (code "69") (name "unconnected-(J7-Pad5)") (class "Default")
      (node (ref "J7") (pin "5") (pinfunction "5_5") (pintype "passive"))
    )
    (net (code "70") (name "unconnected-(U2-ANT_DETECT-PadP4)") (class "Default")
      (node (ref "U2") (pin "P4") (pinfunction "ANT_DETECT_P4") (pintype "input"))
    )
    (net (code "71") (name "unconnected-(U2-ANT_OFF-PadP5)") (class "Default")
      (node (ref "U2") (pin "P5") (pinfunction "ANT_OFF_P5") (pintype "output"))
    )
    (net (code "72") (name "unconnected-(U2-RSVD-PadP8)") (class "Default")
      (node (ref "U2") (pin "P8") (pinfunction "RSVD_P8") (pintype "no_connect"))
    )
    (net (code "73") (name "unconnected-(U2-RSVD-PadP9)") (class "Default")
      (node (ref "U2") (pin "P9") (pinfunction "RSVD_P9") (pintype "no_connect"))
    )
    (net (code "74") (name "unconnected-(U2-RSVD-PadP10)") (class "Default")
      (node (ref "U2") (pin "P10") (pinfunction "RSVD_P10") (pintype "no_connect"))
    )
    (net (code "75") (name "unconnected-(U2-RSVD-PadP11)") (class "Default")
      (node (ref "U2") (pin "P11") (pinfunction "RSVD_P11") (pintype "no_connect"))
    )
    (net (code "76") (name "unconnected-(U2-RSVD-PadP13)") (class "Default")
      (node (ref "U2") (pin "P13") (pinfunction "RSVD_P13") (pintype "no_connect"))
    )
    (net (code "77") (name "unconnected-(U2-RSVD-PadP15)") (class "Default")
      (node (ref "U2") (pin "P15") (pinfunction "RSVD_P15") (pintype "no_connect"))
    )
    (net (code "78") (name "unconnected-(U2-RSVD-PadP16)") (class "Default")
      (node (ref "U2") (pin "P16") (pinfunction "RSVD_P16") (pintype "no_connect"))
    )
    (net (code "79") (name "unconnected-(U2-RSVD-PadP17)") (class "Default")
      (node (ref "U2") (pin "P17") (pinfunction "RSVD_P17") (pintype "no_connect"))
    )
    (net (code "80") (name "unconnected-(U2-RSVD-PadP18)") (class "Default")
      (node (ref "U2") (pin "P18") (pinfunction "RSVD_P18") (pintype "no_connect"))
    )
    (net (code "81") (name "unconnected-(U2-RSVD-PadP21)") (class "Default")
      (node (ref "U2") (pin "P21") (pinfunction "RSVD_P21") (pintype "no_connect"))
    )
    (net (code "82") (name "unconnected-(U2-RSVD-PadP24)") (class "Default")
      (node (ref "U2") (pin "P24") (pinfunction "RSVD_P24") (pintype "no_connect"))
    )
    (net (code "83") (name "unconnected-(U2-RSVD-PadP25)") (class "Default")
      (node (ref "U2") (pin "P25") (pinfunction "RSVD_P25") (pintype "no_connect"))
    )
    (net (code "84") (name "unconnected-(U2-RSVD-PadP28)") (class "Default")
      (node (ref "U2") (pin "P28") (pinfunction "RSVD_P28") (pintype "no_connect"))
    )
    (net (code "85") (name "unconnected-(U2-RSVD-PadP29)") (class "Default")
      (node (ref "U2") (pin "P29") (pinfunction "RSVD_P29") (pintype "no_connect"))
    )
    (net (code "86") (name "unconnected-(U2-RSVD-PadP30)") (class "Default")
      (node (ref "U2") (pin "P30") (pinfunction "RSVD_P30") (pintype "no_connect"))
    )
    (net (code "87") (name "unconnected-(U2-RSVD-PadP31)") (class "Default")
      (node (ref "U2") (pin "P31") (pinfunction "RSVD_P31") (pintype "no_connect"))
    )
    (net (code "88") (name "unconnected-(U2-RSVD-PadP35)") (class "Default")
      (node (ref "U2") (pin "P35") (pinfunction "RSVD_P35") (pintype "no_connect"))
    )
    (net (code "89") (name "unconnected-(U2-RSVD-PadP52)") (class "Default")
      (node (ref "U2") (pin "P52") (pinfunction "RSVD_P52") (pintype "no_connect"))
    )
    (net (code "90") (name "unconnected-(U2-RSVD-PadP54)") (class "Default")
      (node (ref "U2") (pin "P54") (pinfunction "RSVD_P54") (pintype "no_connect"))
    )
    (net (code "91") (name "unconnected-(U2-~{ANT_SHORT}-PadP6)") (class "Default")
      (node (ref "U2") (pin "P6") (pinfunction "~{ANT_SHORT}_P6") (pintype "output"))
    )
  )
)
